# SDRAM_DDR3_2x16.net
KiCad netlist of a schematic drawn in Altium Designer
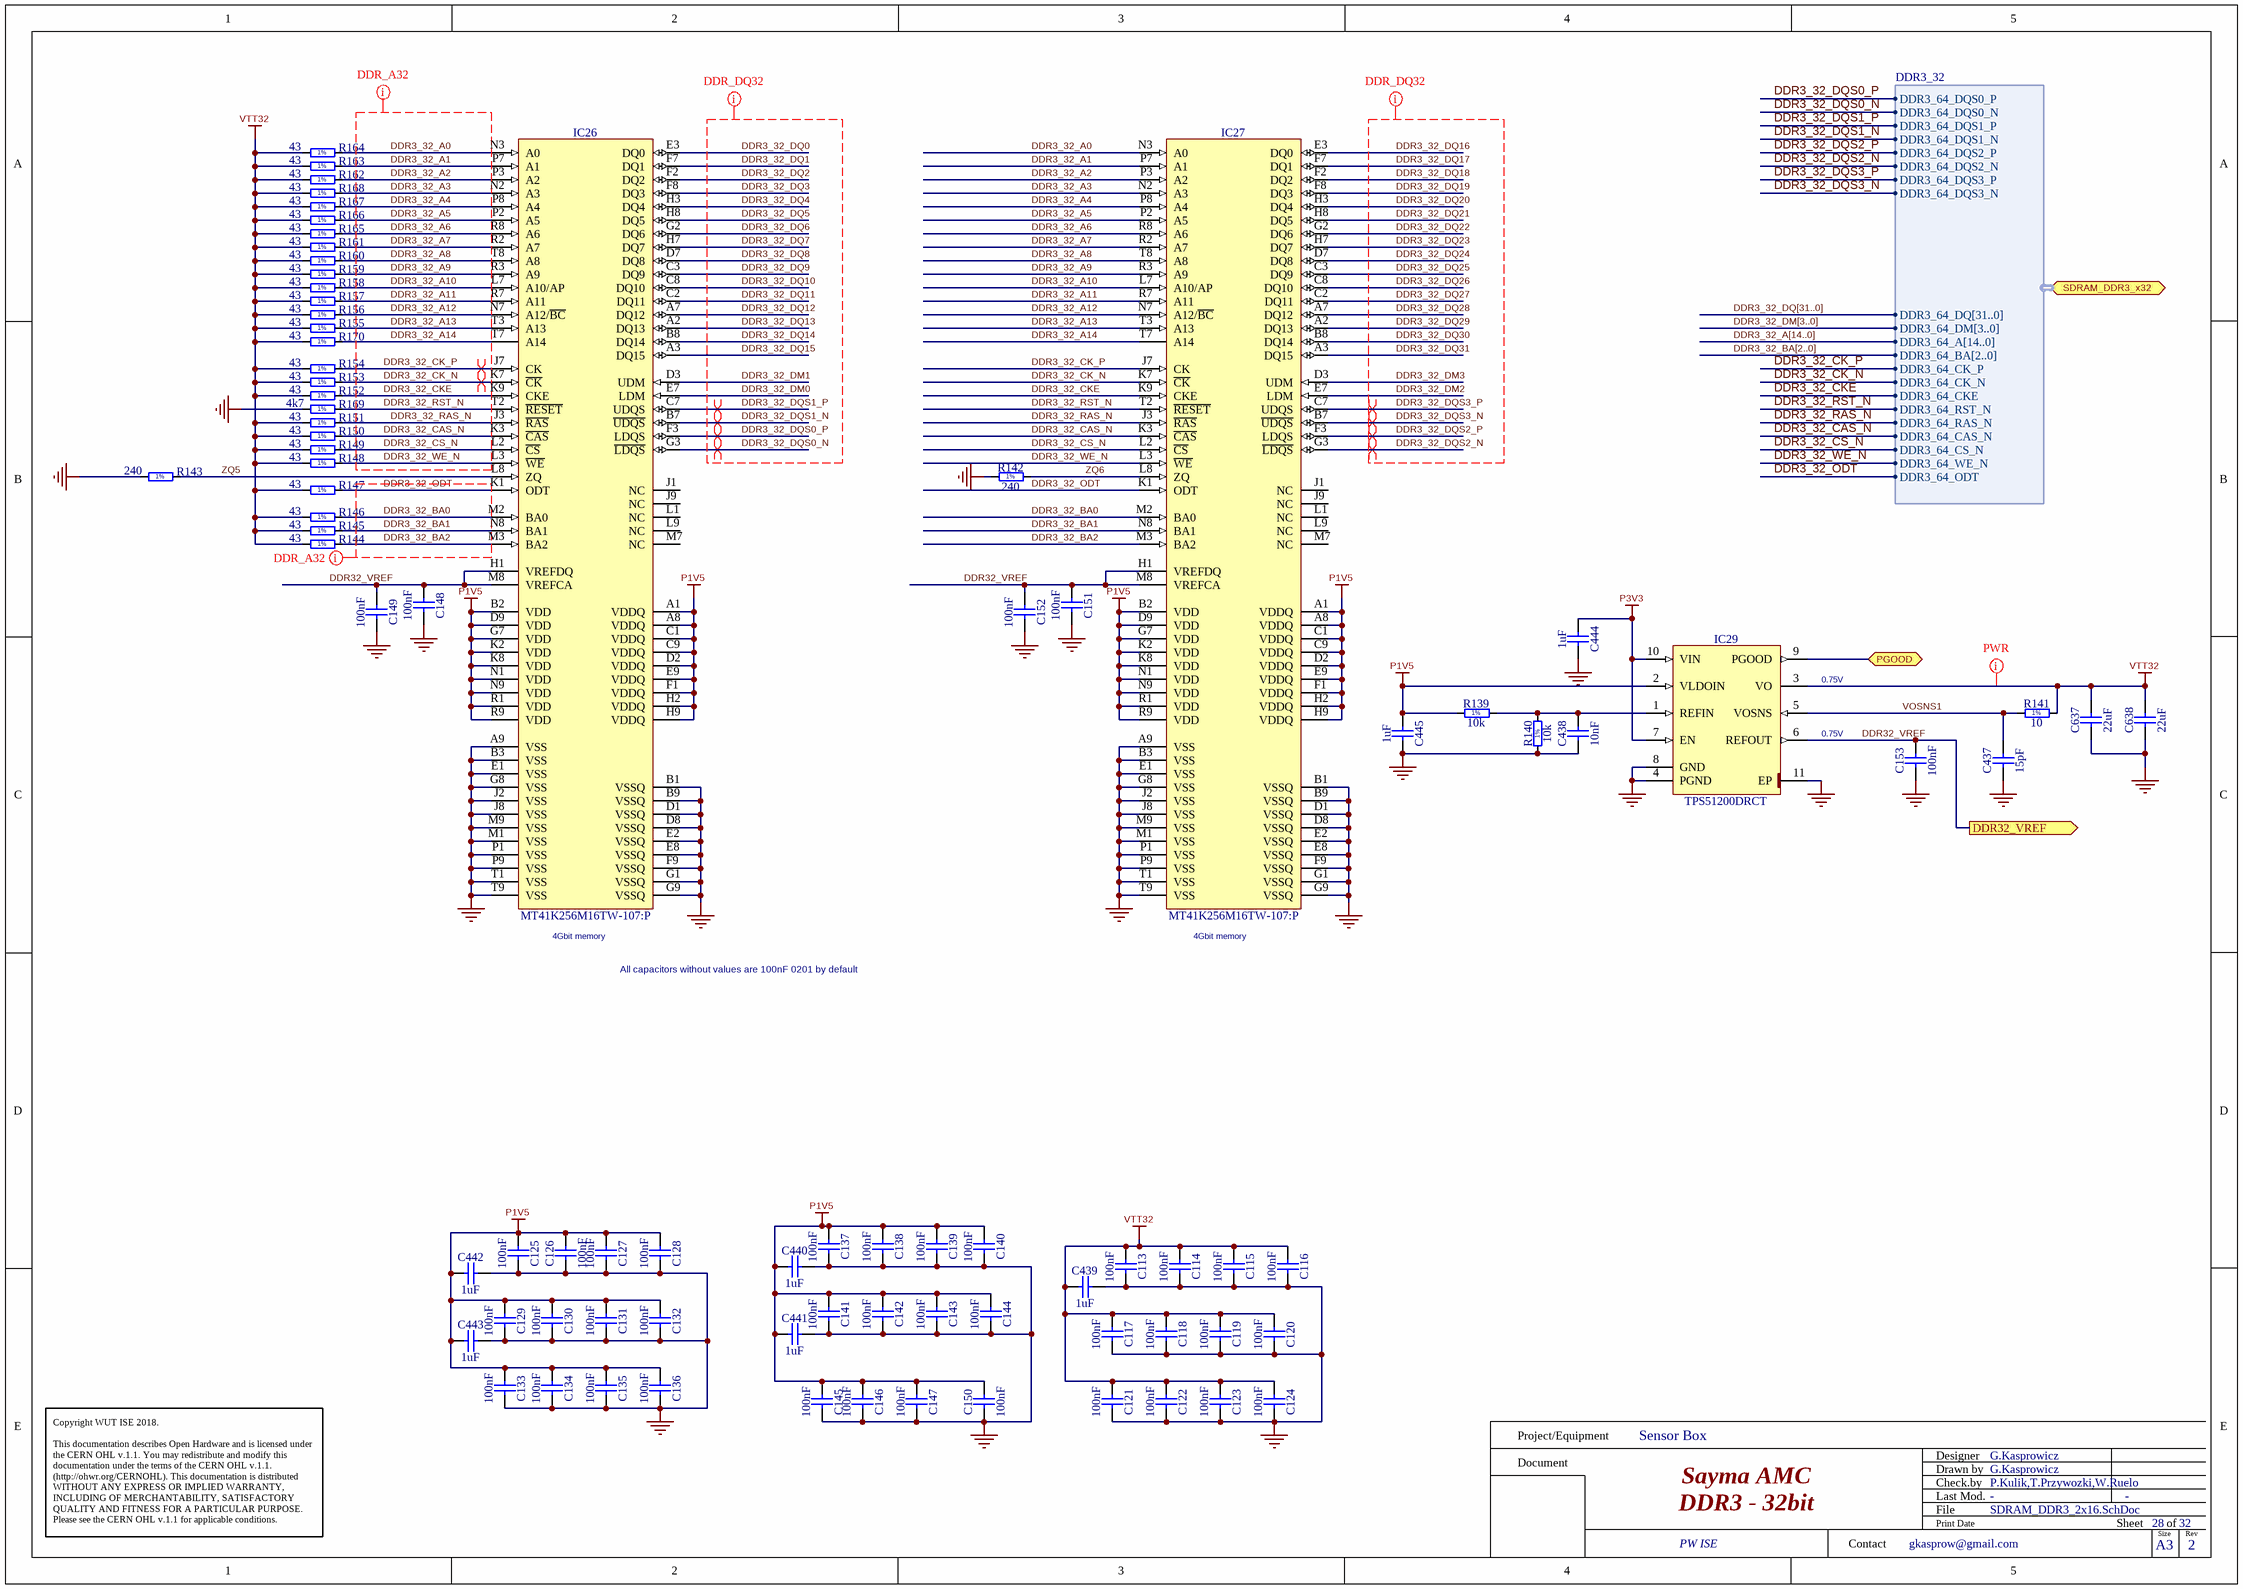
[diagram p0: SDRAM_DDR3_2x16.SchDoc]

(export (version "E")
  (design (tool "Eeschema 10.0.6"))
  (components
    (comp (ref "C113")
      (value "100nF")
      (footprint "CAPC0603X33N")
      (description "Non-polarised capacitor")
      (fields
        (field (name "MANUFACTURER PART NUMBER") "CC0201_100NF_6.3V_10%_X5R")
        (field (name "MANUFACTURER") "GENERIC")
        (field (name "AUTHOR") "CERN DEM JLC")
      )
      (libsource (lib "Capacitors") (part "Capacitor - non polarized"))
    )
    (comp (ref "C114")
      (value "100nF")
      (footprint "CAPC0603X33N")
      (description "Non-polarised capacitor")
      (fields
        (field (name "MANUFACTURER PART NUMBER") "CC0201_100NF_6.3V_10%_X5R")
        (field (name "MANUFACTURER") "GENERIC")
        (field (name "AUTHOR") "CERN DEM JLC")
      )
      (libsource (lib "Capacitors") (part "Capacitor - non polarized"))
    )
    (comp (ref "C115")
      (value "100nF")
      (footprint "CAPC0603X33N")
      (description "Non-polarised capacitor")
      (fields
        (field (name "MANUFACTURER PART NUMBER") "CC0201_100NF_6.3V_10%_X5R")
        (field (name "MANUFACTURER") "GENERIC")
        (field (name "AUTHOR") "CERN DEM JLC")
      )
      (libsource (lib "Capacitors") (part "Capacitor - non polarized"))
    )
    (comp (ref "C116")
      (value "100nF")
      (footprint "CAPC0603X33N")
      (description "Non-polarised capacitor")
      (fields
        (field (name "MANUFACTURER PART NUMBER") "CC0201_100NF_6.3V_10%_X5R")
        (field (name "MANUFACTURER") "GENERIC")
        (field (name "AUTHOR") "CERN DEM JLC")
      )
      (libsource (lib "Capacitors") (part "Capacitor - non polarized"))
    )
    (comp (ref "C117")
      (value "100nF")
      (footprint "CAPC0603X33N")
      (description "Non-polarised capacitor")
      (fields
        (field (name "MANUFACTURER PART NUMBER") "CC0201_100NF_6.3V_10%_X5R")
        (field (name "MANUFACTURER") "GENERIC")
        (field (name "AUTHOR") "CERN DEM JLC")
      )
      (libsource (lib "Capacitors") (part "Capacitor - non polarized"))
    )
    (comp (ref "C118")
      (value "100nF")
      (footprint "CAPC0603X33N")
      (description "Non-polarised capacitor")
      (fields
        (field (name "MANUFACTURER PART NUMBER") "CC0201_100NF_6.3V_10%_X5R")
        (field (name "MANUFACTURER") "GENERIC")
        (field (name "AUTHOR") "CERN DEM JLC")
      )
      (libsource (lib "Capacitors") (part "Capacitor - non polarized"))
    )
    (comp (ref "C119")
      (value "100nF")
      (footprint "CAPC0603X33N")
      (description "Non-polarised capacitor")
      (fields
        (field (name "MANUFACTURER PART NUMBER") "CC0201_100NF_6.3V_10%_X5R")
        (field (name "MANUFACTURER") "GENERIC")
        (field (name "AUTHOR") "CERN DEM JLC")
      )
      (libsource (lib "Capacitors") (part "Capacitor - non polarized"))
    )
    (comp (ref "C120")
      (value "100nF")
      (footprint "CAPC0603X33N")
      (description "Non-polarised capacitor")
      (fields
        (field (name "MANUFACTURER PART NUMBER") "CC0201_100NF_6.3V_10%_X5R")
        (field (name "MANUFACTURER") "GENERIC")
        (field (name "AUTHOR") "CERN DEM JLC")
      )
      (libsource (lib "Capacitors") (part "Capacitor - non polarized"))
    )
    (comp (ref "C121")
      (value "100nF")
      (footprint "CAPC0603X33N")
      (description "Non-polarised capacitor")
      (fields
        (field (name "MANUFACTURER PART NUMBER") "CC0201_100NF_6.3V_10%_X5R")
        (field (name "MANUFACTURER") "GENERIC")
        (field (name "AUTHOR") "CERN DEM JLC")
      )
      (libsource (lib "Capacitors") (part "Capacitor - non polarized"))
    )
    (comp (ref "C122")
      (value "100nF")
      (footprint "CAPC0603X33N")
      (description "Non-polarised capacitor")
      (fields
        (field (name "MANUFACTURER PART NUMBER") "CC0201_100NF_6.3V_10%_X5R")
        (field (name "MANUFACTURER") "GENERIC")
        (field (name "AUTHOR") "CERN DEM JLC")
      )
      (libsource (lib "Capacitors") (part "Capacitor - non polarized"))
    )
    (comp (ref "C123")
      (value "100nF")
      (footprint "CAPC0603X33N")
      (description "Non-polarised capacitor")
      (fields
        (field (name "MANUFACTURER PART NUMBER") "CC0201_100NF_6.3V_10%_X5R")
        (field (name "MANUFACTURER") "GENERIC")
        (field (name "AUTHOR") "CERN DEM JLC")
      )
      (libsource (lib "Capacitors") (part "Capacitor - non polarized"))
    )
    (comp (ref "C124")
      (value "100nF")
      (footprint "CAPC0603X33N")
      (description "Non-polarised capacitor")
      (fields
        (field (name "MANUFACTURER PART NUMBER") "CC0201_100NF_6.3V_10%_X5R")
        (field (name "MANUFACTURER") "GENERIC")
        (field (name "AUTHOR") "CERN DEM JLC")
      )
      (libsource (lib "Capacitors") (part "Capacitor - non polarized"))
    )
    (comp (ref "C125")
      (value "100nF")
      (footprint "CAPC0603X33N")
      (description "Non-polarised capacitor")
      (fields
        (field (name "MANUFACTURER PART NUMBER") "CC0201_100NF_6.3V_10%_X5R")
        (field (name "MANUFACTURER") "GENERIC")
        (field (name "AUTHOR") "CERN DEM JLC")
      )
      (libsource (lib "Capacitors") (part "Capacitor - non polarized"))
    )
    (comp (ref "C126")
      (value "100nF")
      (footprint "CAPC0603X33N")
      (description "Non-polarised capacitor")
      (fields
        (field (name "MANUFACTURER PART NUMBER") "CC0201_100NF_6.3V_10%_X5R")
        (field (name "MANUFACTURER") "GENERIC")
        (field (name "AUTHOR") "CERN DEM JLC")
      )
      (libsource (lib "Capacitors") (part "Capacitor - non polarized"))
    )
    (comp (ref "C127")
      (value "100nF")
      (footprint "CAPC0603X33N")
      (description "Non-polarised capacitor")
      (fields
        (field (name "MANUFACTURER PART NUMBER") "CC0201_100NF_6.3V_10%_X5R")
        (field (name "MANUFACTURER") "GENERIC")
        (field (name "AUTHOR") "CERN DEM JLC")
      )
      (libsource (lib "Capacitors") (part "Capacitor - non polarized"))
    )
    (comp (ref "C128")
      (value "100nF")
      (footprint "CAPC0603X33N")
      (description "Non-polarised capacitor")
      (fields
        (field (name "MANUFACTURER PART NUMBER") "CC0201_100NF_6.3V_10%_X5R")
        (field (name "MANUFACTURER") "GENERIC")
        (field (name "AUTHOR") "CERN DEM JLC")
      )
      (libsource (lib "Capacitors") (part "Capacitor - non polarized"))
    )
    (comp (ref "C129")
      (value "100nF")
      (footprint "CAPC0603X33N")
      (description "Non-polarised capacitor")
      (fields
        (field (name "MANUFACTURER PART NUMBER") "CC0201_100NF_6.3V_10%_X5R")
        (field (name "MANUFACTURER") "GENERIC")
        (field (name "AUTHOR") "CERN DEM JLC")
      )
      (libsource (lib "Capacitors") (part "Capacitor - non polarized"))
    )
    (comp (ref "C130")
      (value "100nF")
      (footprint "CAPC0603X33N")
      (description "Non-polarised capacitor")
      (fields
        (field (name "MANUFACTURER PART NUMBER") "CC0201_100NF_6.3V_10%_X5R")
        (field (name "MANUFACTURER") "GENERIC")
        (field (name "AUTHOR") "CERN DEM JLC")
      )
      (libsource (lib "Capacitors") (part "Capacitor - non polarized"))
    )
    (comp (ref "C131")
      (value "100nF")
      (footprint "CAPC0603X33N")
      (description "Non-polarised capacitor")
      (fields
        (field (name "MANUFACTURER PART NUMBER") "CC0201_100NF_6.3V_10%_X5R")
        (field (name "MANUFACTURER") "GENERIC")
        (field (name "AUTHOR") "CERN DEM JLC")
      )
      (libsource (lib "Capacitors") (part "Capacitor - non polarized"))
    )
    (comp (ref "C132")
      (value "100nF")
      (footprint "CAPC0603X33N")
      (description "Non-polarised capacitor")
      (fields
        (field (name "MANUFACTURER PART NUMBER") "CC0201_100NF_6.3V_10%_X5R")
        (field (name "MANUFACTURER") "GENERIC")
        (field (name "AUTHOR") "CERN DEM JLC")
      )
      (libsource (lib "Capacitors") (part "Capacitor - non polarized"))
    )
    (comp (ref "C133")
      (value "100nF")
      (footprint "CAPC0603X33N")
      (description "Non-polarised capacitor")
      (fields
        (field (name "MANUFACTURER PART NUMBER") "CC0201_100NF_6.3V_10%_X5R")
        (field (name "MANUFACTURER") "GENERIC")
        (field (name "AUTHOR") "CERN DEM JLC")
      )
      (libsource (lib "Capacitors") (part "Capacitor - non polarized"))
    )
    (comp (ref "C134")
      (value "100nF")
      (footprint "CAPC0603X33N")
      (description "Non-polarised capacitor")
      (fields
        (field (name "MANUFACTURER PART NUMBER") "CC0201_100NF_6.3V_10%_X5R")
        (field (name "MANUFACTURER") "GENERIC")
        (field (name "AUTHOR") "CERN DEM JLC")
      )
      (libsource (lib "Capacitors") (part "Capacitor - non polarized"))
    )
    (comp (ref "C135")
      (value "100nF")
      (footprint "CAPC0603X33N")
      (description "Non-polarised capacitor")
      (fields
        (field (name "MANUFACTURER PART NUMBER") "CC0201_100NF_6.3V_10%_X5R")
        (field (name "MANUFACTURER") "GENERIC")
        (field (name "AUTHOR") "CERN DEM JLC")
      )
      (libsource (lib "Capacitors") (part "Capacitor - non polarized"))
    )
    (comp (ref "C136")
      (value "100nF")
      (footprint "CAPC0603X33N")
      (description "Non-polarised capacitor")
      (fields
        (field (name "MANUFACTURER PART NUMBER") "CC0201_100NF_6.3V_10%_X5R")
        (field (name "MANUFACTURER") "GENERIC")
        (field (name "AUTHOR") "CERN DEM JLC")
      )
      (libsource (lib "Capacitors") (part "Capacitor - non polarized"))
    )
    (comp (ref "C137")
      (value "100nF")
      (footprint "CAPC0603X33N")
      (description "Non-polarised capacitor")
      (fields
        (field (name "MANUFACTURER PART NUMBER") "CC0201_100NF_6.3V_10%_X5R")
        (field (name "MANUFACTURER") "GENERIC")
        (field (name "AUTHOR") "CERN DEM JLC")
      )
      (libsource (lib "Capacitors") (part "Capacitor - non polarized"))
    )
    (comp (ref "C138")
      (value "100nF")
      (footprint "CAPC0603X33N")
      (description "Non-polarised capacitor")
      (fields
        (field (name "MANUFACTURER PART NUMBER") "CC0201_100NF_6.3V_10%_X5R")
        (field (name "MANUFACTURER") "GENERIC")
        (field (name "AUTHOR") "CERN DEM JLC")
      )
      (libsource (lib "Capacitors") (part "Capacitor - non polarized"))
    )
    (comp (ref "C139")
      (value "100nF")
      (footprint "CAPC0603X33N")
      (description "Non-polarised capacitor")
      (fields
        (field (name "MANUFACTURER PART NUMBER") "CC0201_100NF_6.3V_10%_X5R")
        (field (name "MANUFACTURER") "GENERIC")
        (field (name "AUTHOR") "CERN DEM JLC")
      )
      (libsource (lib "Capacitors") (part "Capacitor - non polarized"))
    )
    (comp (ref "C140")
      (value "100nF")
      (footprint "CAPC0603X33N")
      (description "Non-polarised capacitor")
      (fields
        (field (name "MANUFACTURER PART NUMBER") "CC0201_100NF_6.3V_10%_X5R")
        (field (name "MANUFACTURER") "GENERIC")
        (field (name "AUTHOR") "CERN DEM JLC")
      )
      (libsource (lib "Capacitors") (part "Capacitor - non polarized"))
    )
    (comp (ref "C141")
      (value "100nF")
      (footprint "CAPC0603X33N")
      (description "Non-polarised capacitor")
      (fields
        (field (name "MANUFACTURER PART NUMBER") "CC0201_100NF_6.3V_10%_X5R")
        (field (name "MANUFACTURER") "GENERIC")
        (field (name "AUTHOR") "CERN DEM JLC")
      )
      (libsource (lib "Capacitors") (part "Capacitor - non polarized"))
    )
    (comp (ref "C142")
      (value "100nF")
      (footprint "CAPC0603X33N")
      (description "Non-polarised capacitor")
      (fields
        (field (name "MANUFACTURER PART NUMBER") "CC0201_100NF_6.3V_10%_X5R")
        (field (name "MANUFACTURER") "GENERIC")
        (field (name "AUTHOR") "CERN DEM JLC")
      )
      (libsource (lib "Capacitors") (part "Capacitor - non polarized"))
    )
    (comp (ref "C143")
      (value "100nF")
      (footprint "CAPC0603X33N")
      (description "Non-polarised capacitor")
      (fields
        (field (name "MANUFACTURER PART NUMBER") "CC0201_100NF_6.3V_10%_X5R")
        (field (name "MANUFACTURER") "GENERIC")
        (field (name "AUTHOR") "CERN DEM JLC")
      )
      (libsource (lib "Capacitors") (part "Capacitor - non polarized"))
    )
    (comp (ref "C144")
      (value "100nF")
      (footprint "CAPC0603X33N")
      (description "Non-polarised capacitor")
      (fields
        (field (name "MANUFACTURER PART NUMBER") "CC0201_100NF_6.3V_10%_X5R")
        (field (name "MANUFACTURER") "GENERIC")
        (field (name "AUTHOR") "CERN DEM JLC")
      )
      (libsource (lib "Capacitors") (part "Capacitor - non polarized"))
    )
    (comp (ref "C145")
      (value "100nF")
      (footprint "CAPC0603X33N")
      (description "Non-polarised capacitor")
      (fields
        (field (name "MANUFACTURER PART NUMBER") "CC0201_100NF_6.3V_10%_X5R")
        (field (name "MANUFACTURER") "GENERIC")
        (field (name "AUTHOR") "CERN DEM JLC")
      )
      (libsource (lib "Capacitors") (part "Capacitor - non polarized"))
    )
    (comp (ref "C146")
      (value "100nF")
      (footprint "CAPC0603X33N")
      (description "Non-polarised capacitor")
      (fields
        (field (name "MANUFACTURER PART NUMBER") "CC0201_100NF_6.3V_10%_X5R")
        (field (name "MANUFACTURER") "GENERIC")
        (field (name "AUTHOR") "CERN DEM JLC")
      )
      (libsource (lib "Capacitors") (part "Capacitor - non polarized"))
    )
    (comp (ref "C147")
      (value "100nF")
      (footprint "CAPC0603X33N")
      (description "Non-polarised capacitor")
      (fields
        (field (name "MANUFACTURER PART NUMBER") "CC0201_100NF_6.3V_10%_X5R")
        (field (name "MANUFACTURER") "GENERIC")
        (field (name "AUTHOR") "CERN DEM JLC")
      )
      (libsource (lib "Capacitors") (part "Capacitor - non polarized"))
    )
    (comp (ref "C148")
      (value "100nF")
      (footprint "CAPC0603X33N")
      (description "Non-polarised capacitor")
      (fields
        (field (name "MANUFACTURER PART NUMBER") "CC0201_100NF_6.3V_10%_X5R")
        (field (name "MANUFACTURER") "GENERIC")
        (field (name "AUTHOR") "CERN DEM JLC")
      )
      (libsource (lib "Capacitors") (part "Capacitor - non polarized"))
    )
    (comp (ref "C149")
      (value "100nF")
      (footprint "CAPC0603X33N")
      (description "Non-polarised capacitor")
      (fields
        (field (name "MANUFACTURER PART NUMBER") "CC0201_100NF_6.3V_10%_X5R")
        (field (name "MANUFACTURER") "GENERIC")
        (field (name "AUTHOR") "CERN DEM JLC")
      )
      (libsource (lib "Capacitors") (part "Capacitor - non polarized"))
    )
    (comp (ref "C150")
      (value "100nF")
      (footprint "CAPC0603X33N")
      (description "Non-polarised capacitor")
      (fields
        (field (name "MANUFACTURER PART NUMBER") "CC0201_100NF_6.3V_10%_X5R")
        (field (name "MANUFACTURER") "GENERIC")
        (field (name "AUTHOR") "CERN DEM JLC")
      )
      (libsource (lib "Capacitors") (part "Capacitor - non polarized"))
    )
    (comp (ref "C151")
      (value "100nF")
      (footprint "CAPC0603X33N")
      (description "Non-polarised capacitor")
      (fields
        (field (name "MANUFACTURER PART NUMBER") "CC0201_100NF_6.3V_10%_X5R")
        (field (name "MANUFACTURER") "GENERIC")
        (field (name "AUTHOR") "CERN DEM JLC")
      )
      (libsource (lib "Capacitors") (part "Capacitor - non polarized"))
    )
    (comp (ref "C152")
      (value "100nF")
      (footprint "CAPC0603X33N")
      (description "Non-polarised capacitor")
      (fields
        (field (name "MANUFACTURER PART NUMBER") "CC0201_100NF_6.3V_10%_X5R")
        (field (name "MANUFACTURER") "GENERIC")
        (field (name "AUTHOR") "CERN DEM JLC")
      )
      (libsource (lib "Capacitors") (part "Capacitor - non polarized"))
    )
    (comp (ref "C153")
      (value "100nF")
      (footprint "CAPC0603X33N")
      (description "Non-polarised capacitor")
      (fields
        (field (name "MANUFACTURER PART NUMBER") "CC0201_100NF_6.3V_10%_X5R")
        (field (name "MANUFACTURER") "GENERIC")
        (field (name "AUTHOR") "CERN DEM JLC")
      )
      (libsource (lib "Capacitors") (part "Capacitor - non polarized"))
    )
    (comp (ref "C437")
      (value "15pF")
      (footprint "CAPC1005X55N")
      (description "Non-polarised capacitor")
      (fields
        (field (name "MANUFACTURER PART NUMBER") "CC0402_15PF_50V_5%_C0G")
        (field (name "MANUFACTURER") "GENERIC")
        (field (name "AUTHOR") "CERN DEM JLC")
      )
      (libsource (lib "Capacitors") (part "Capacitor - non polarized"))
    )
    (comp (ref "C438")
      (value "10nF")
      (footprint "CAPC1005X55N")
      (description "Non-polarised capacitor")
      (fields
        (field (name "MANUFACTURER PART NUMBER") "CC0402_10NF_25V_10%_X7R")
        (field (name "MANUFACTURER") "GENERIC")
        (field (name "AUTHOR") "CERN DEM JLC")
      )
      (libsource (lib "Capacitors") (part "Capacitor - non polarized"))
    )
    (comp (ref "C439")
      (value "1uF")
      (footprint "CAPC1005X55N")
      (description "Non-polarised capacitor")
      (fields
        (field (name "MANUFACTURER PART NUMBER") "CC0402_1UF_16V_10%_X5R")
        (field (name "MANUFACTURER") "GENERIC")
        (field (name "AUTHOR") "CERN DEM JLC")
      )
      (libsource (lib "Capacitors") (part "Capacitor - non polarized"))
    )
    (comp (ref "C440")
      (value "1uF")
      (footprint "CAPC1005X55N")
      (description "Non-polarised capacitor")
      (fields
        (field (name "MANUFACTURER PART NUMBER") "CC0402_1UF_16V_10%_X5R")
        (field (name "MANUFACTURER") "GENERIC")
        (field (name "AUTHOR") "CERN DEM JLC")
      )
      (libsource (lib "Capacitors") (part "Capacitor - non polarized"))
    )
    (comp (ref "C441")
      (value "1uF")
      (footprint "CAPC1005X55N")
      (description "Non-polarised capacitor")
      (fields
        (field (name "MANUFACTURER PART NUMBER") "CC0402_1UF_16V_10%_X5R")
        (field (name "MANUFACTURER") "GENERIC")
        (field (name "AUTHOR") "CERN DEM JLC")
      )
      (libsource (lib "Capacitors") (part "Capacitor - non polarized"))
    )
    (comp (ref "C442")
      (value "1uF")
      (footprint "CAPC1005X55N")
      (description "Non-polarised capacitor")
      (fields
        (field (name "MANUFACTURER PART NUMBER") "CC0402_1UF_16V_10%_X5R")
        (field (name "MANUFACTURER") "GENERIC")
        (field (name "AUTHOR") "CERN DEM JLC")
      )
      (libsource (lib "Capacitors") (part "Capacitor - non polarized"))
    )
    (comp (ref "C443")
      (value "1uF")
      (footprint "CAPC1005X55N")
      (description "Non-polarised capacitor")
      (fields
        (field (name "MANUFACTURER PART NUMBER") "CC0402_1UF_16V_10%_X5R")
        (field (name "MANUFACTURER") "GENERIC")
        (field (name "AUTHOR") "CERN DEM JLC")
      )
      (libsource (lib "Capacitors") (part "Capacitor - non polarized"))
    )
    (comp (ref "C444")
      (value "1uF")
      (footprint "CAPC1005X55N")
      (description "Non-polarised capacitor")
      (fields
        (field (name "MANUFACTURER PART NUMBER") "CC0402_1UF_16V_10%_X5R")
        (field (name "MANUFACTURER") "GENERIC")
        (field (name "AUTHOR") "CERN DEM JLC")
      )
      (libsource (lib "Capacitors") (part "Capacitor - non polarized"))
    )
    (comp (ref "C445")
      (value "1uF")
      (footprint "CAPC1005X55N")
      (description "Non-polarised capacitor")
      (fields
        (field (name "MANUFACTURER PART NUMBER") "CC0402_1UF_16V_10%_X5R")
        (field (name "MANUFACTURER") "GENERIC")
        (field (name "AUTHOR") "CERN DEM JLC")
      )
      (libsource (lib "Capacitors") (part "Capacitor - non polarized"))
    )
    (comp (ref "C637")
      (value "22uF")
      (footprint "CAPC2012X135N")
      (description "Non-polarised capacitor")
      (fields
        (field (name "MANUFACTURER PART NUMBER") "CC0805_22UF_10V_+80%-20%_Y5V")
        (field (name "MANUFACTURER") "GENERIC")
        (field (name "AUTHOR") "CERN DEM JLC")
      )
      (libsource (lib "Capacitors") (part "Capacitor - non polarized"))
    )
    (comp (ref "C638")
      (value "22uF")
      (footprint "CAPC2012X135N")
      (description "Non-polarised capacitor")
      (fields
        (field (name "MANUFACTURER PART NUMBER") "CC0805_22UF_10V_+80%-20%_Y5V")
        (field (name "MANUFACTURER") "GENERIC")
        (field (name "AUTHOR") "CERN DEM JLC")
      )
      (libsource (lib "Capacitors") (part "Capacitor - non polarized"))
    )
    (comp (ref "IC26")
      (value "MT41K256M16TW-107:P")
      (footprint "BGA96C80P9X16_800X1400X120")
      (description "32 Meg x 16 x 8 Banks DDR3L SDRAM")
      (fields (field (name "MANUFACTURER") "MICRON TECHNOLOGY") (field (name "AUTHOR") "CERN DEM MR"))
      (libsource (lib "ICs And Semiconductors") (part "MT41K256M16TW-107{colon}P"))
    )
    (comp (ref "IC27")
      (value "MT41K256M16TW-107:P")
      (footprint "BGA96C80P9X16_800X1400X120")
      (description "32 Meg x 16 x 8 Banks DDR3L SDRAM")
      (fields (field (name "MANUFACTURER") "MICRON TECHNOLOGY") (field (name "AUTHOR") "CERN DEM MR"))
      (libsource (lib "ICs And Semiconductors") (part "MT41K256M16TW-107{colon}P"))
    )
    (comp (ref "IC29")
      (value "TPS51200DRCT")
      (footprint "TEXAS_DRC (S-PVSON-N10)")
      (description "Sink/Source DDR Termination Regulator")
      (fields (field (name "MANUFACTURER") "TEXAS INSTRUMENTS") (field (name "AUTHOR") "CERN DEM JLC"))
      (libsource (lib "ICs And Semiconductors") (part "TPS51200DRC"))
    )
    (comp (ref "R139")
      (value "10k")
      (footprint "RESC1005X40N")
      (description "Resistor - 1%")
      (fields
        (field (name "MANUFACTURER PART NUMBER") "R0402_10K_1%_0.0625W_100PPM")
        (field (name "MANUFACTURER") "GENERIC")
        (field (name "AUTHOR") "CERN DEM JLC")
      )
      (libsource (lib "Resistors") (part "Resistor - 1%"))
    )
    (comp (ref "R140")
      (value "10k")
      (footprint "RESC1005X40N")
      (description "Resistor - 1%")
      (fields
        (field (name "MANUFACTURER PART NUMBER") "R0402_10K_1%_0.0625W_100PPM")
        (field (name "MANUFACTURER") "GENERIC")
        (field (name "AUTHOR") "CERN DEM JLC")
      )
      (libsource (lib "Resistors") (part "Resistor - 1%"))
    )
    (comp (ref "R141")
      (value "10")
      (footprint "RESC1005X40N")
      (description "Resistor - 1%")
      (fields
        (field (name "MANUFACTURER PART NUMBER") "R0402_10R_1%_0.0625W_200PPM")
        (field (name "MANUFACTURER") "GENERIC")
        (field (name "AUTHOR") "CERN DEM JLC")
      )
      (libsource (lib "Resistors") (part "Resistor - 1%"))
    )
    (comp (ref "R142")
      (value "240")
      (footprint "RESC1005X40N")
      (description "Resistor - 1%")
      (fields
        (field (name "MANUFACTURER PART NUMBER") "R0402_240R_1%_0.0625W_100PPM")
        (field (name "MANUFACTURER") "GENERIC")
        (field (name "AUTHOR") "CERN DEM JLC")
      )
      (libsource (lib "Resistors") (part "Resistor - 1%"))
    )
    (comp (ref "R143")
      (value "240")
      (footprint "RESC1005X40N")
      (description "Resistor - 1%")
      (fields
        (field (name "MANUFACTURER PART NUMBER") "R0402_240R_1%_0.0625W_100PPM")
        (field (name "MANUFACTURER") "GENERIC")
        (field (name "AUTHOR") "CERN DEM JLC")
      )
      (libsource (lib "Resistors") (part "Resistor - 1%"))
    )
    (comp (ref "R144")
      (value "43")
      (footprint "RESC1005X40N")
      (description "Resistor - 1%")
      (fields
        (field (name "MANUFACTURER PART NUMBER") "R0402_43R_1%_0.0625W_100PPM")
        (field (name "MANUFACTURER") "GENERIC")
        (field (name "AUTHOR") "CERN DEM JLC")
      )
      (libsource (lib "Resistors") (part "Resistor - 1%"))
    )
    (comp (ref "R145")
      (value "43")
      (footprint "RESC1005X40N")
      (description "Resistor - 1%")
      (fields
        (field (name "MANUFACTURER PART NUMBER") "R0402_43R_1%_0.0625W_100PPM")
        (field (name "MANUFACTURER") "GENERIC")
        (field (name "AUTHOR") "CERN DEM JLC")
      )
      (libsource (lib "Resistors") (part "Resistor - 1%"))
    )
    (comp (ref "R146")
      (value "43")
      (footprint "RESC1005X40N")
      (description "Resistor - 1%")
      (fields
        (field (name "MANUFACTURER PART NUMBER") "R0402_43R_1%_0.0625W_100PPM")
        (field (name "MANUFACTURER") "GENERIC")
        (field (name "AUTHOR") "CERN DEM JLC")
      )
      (libsource (lib "Resistors") (part "Resistor - 1%"))
    )
    (comp (ref "R147")
      (value "43")
      (footprint "RESC1005X40N")
      (description "Resistor - 1%")
      (fields
        (field (name "MANUFACTURER PART NUMBER") "R0402_43R_1%_0.0625W_100PPM")
        (field (name "MANUFACTURER") "GENERIC")
        (field (name "AUTHOR") "CERN DEM JLC")
      )
      (libsource (lib "Resistors") (part "Resistor - 1%"))
    )
    (comp (ref "R148")
      (value "43")
      (footprint "RESC1005X40N")
      (description "Resistor - 1%")
      (fields
        (field (name "MANUFACTURER PART NUMBER") "R0402_43R_1%_0.0625W_100PPM")
        (field (name "MANUFACTURER") "GENERIC")
        (field (name "AUTHOR") "CERN DEM JLC")
      )
      (libsource (lib "Resistors") (part "Resistor - 1%"))
    )
    (comp (ref "R149")
      (value "43")
      (footprint "RESC1005X40N")
      (description "Resistor - 1%")
      (fields
        (field (name "MANUFACTURER PART NUMBER") "R0402_43R_1%_0.0625W_100PPM")
        (field (name "MANUFACTURER") "GENERIC")
        (field (name "AUTHOR") "CERN DEM JLC")
      )
      (libsource (lib "Resistors") (part "Resistor - 1%"))
    )
    (comp (ref "R150")
      (value "43")
      (footprint "RESC1005X40N")
      (description "Resistor - 1%")
      (fields
        (field (name "MANUFACTURER PART NUMBER") "R0402_43R_1%_0.0625W_100PPM")
        (field (name "MANUFACTURER") "GENERIC")
        (field (name "AUTHOR") "CERN DEM JLC")
      )
      (libsource (lib "Resistors") (part "Resistor - 1%"))
    )
    (comp (ref "R151")
      (value "43")
      (footprint "RESC1005X40N")
      (description "Resistor - 1%")
      (fields
        (field (name "MANUFACTURER PART NUMBER") "R0402_43R_1%_0.0625W_100PPM")
        (field (name "MANUFACTURER") "GENERIC")
        (field (name "AUTHOR") "CERN DEM JLC")
      )
      (libsource (lib "Resistors") (part "Resistor - 1%"))
    )
    (comp (ref "R152")
      (value "43")
      (footprint "RESC1005X40N")
      (description "Resistor - 1%")
      (fields
        (field (name "MANUFACTURER PART NUMBER") "R0402_43R_1%_0.0625W_100PPM")
        (field (name "MANUFACTURER") "GENERIC")
        (field (name "AUTHOR") "CERN DEM JLC")
      )
      (libsource (lib "Resistors") (part "Resistor - 1%"))
    )
    (comp (ref "R153")
      (value "43")
      (footprint "RESC1005X40N")
      (description "Resistor - 1%")
      (fields
        (field (name "MANUFACTURER PART NUMBER") "R0402_43R_1%_0.0625W_100PPM")
        (field (name "MANUFACTURER") "GENERIC")
        (field (name "AUTHOR") "CERN DEM JLC")
      )
      (libsource (lib "Resistors") (part "Resistor - 1%"))
    )
    (comp (ref "R154")
      (value "43")
      (footprint "RESC1005X40N")
      (description "Resistor - 1%")
      (fields
        (field (name "MANUFACTURER PART NUMBER") "R0402_43R_1%_0.0625W_100PPM")
        (field (name "MANUFACTURER") "GENERIC")
        (field (name "AUTHOR") "CERN DEM JLC")
      )
      (libsource (lib "Resistors") (part "Resistor - 1%"))
    )
    (comp (ref "R155")
      (value "43")
      (footprint "RESC1005X40N")
      (description "Resistor - 1%")
      (fields
        (field (name "MANUFACTURER PART NUMBER") "R0402_43R_1%_0.0625W_100PPM")
        (field (name "MANUFACTURER") "GENERIC")
        (field (name "AUTHOR") "CERN DEM JLC")
      )
      (libsource (lib "Resistors") (part "Resistor - 1%"))
    )
    (comp (ref "R156")
      (value "43")
      (footprint "RESC1005X40N")
      (description "Resistor - 1%")
      (fields
        (field (name "MANUFACTURER PART NUMBER") "R0402_43R_1%_0.0625W_100PPM")
        (field (name "MANUFACTURER") "GENERIC")
        (field (name "AUTHOR") "CERN DEM JLC")
      )
      (libsource (lib "Resistors") (part "Resistor - 1%"))
    )
    (comp (ref "R157")
      (value "43")
      (footprint "RESC1005X40N")
      (description "Resistor - 1%")
      (fields
        (field (name "MANUFACTURER PART NUMBER") "R0402_43R_1%_0.0625W_100PPM")
        (field (name "MANUFACTURER") "GENERIC")
        (field (name "AUTHOR") "CERN DEM JLC")
      )
      (libsource (lib "Resistors") (part "Resistor - 1%"))
    )
    (comp (ref "R158")
      (value "43")
      (footprint "RESC1005X40N")
      (description "Resistor - 1%")
      (fields
        (field (name "MANUFACTURER PART NUMBER") "R0402_43R_1%_0.0625W_100PPM")
        (field (name "MANUFACTURER") "GENERIC")
        (field (name "AUTHOR") "CERN DEM JLC")
      )
      (libsource (lib "Resistors") (part "Resistor - 1%"))
    )
    (comp (ref "R159")
      (value "43")
      (footprint "RESC1005X40N")
      (description "Resistor - 1%")
      (fields
        (field (name "MANUFACTURER PART NUMBER") "R0402_43R_1%_0.0625W_100PPM")
        (field (name "MANUFACTURER") "GENERIC")
        (field (name "AUTHOR") "CERN DEM JLC")
      )
      (libsource (lib "Resistors") (part "Resistor - 1%"))
    )
    (comp (ref "R160")
      (value "43")
      (footprint "RESC1005X40N")
      (description "Resistor - 1%")
      (fields
        (field (name "MANUFACTURER PART NUMBER") "R0402_43R_1%_0.0625W_100PPM")
        (field (name "MANUFACTURER") "GENERIC")
        (field (name "AUTHOR") "CERN DEM JLC")
      )
      (libsource (lib "Resistors") (part "Resistor - 1%"))
    )
    (comp (ref "R161")
      (value "43")
      (footprint "RESC1005X40N")
      (description "Resistor - 1%")
      (fields
        (field (name "MANUFACTURER PART NUMBER") "R0402_43R_1%_0.0625W_100PPM")
        (field (name "MANUFACTURER") "GENERIC")
        (field (name "AUTHOR") "CERN DEM JLC")
      )
      (libsource (lib "Resistors") (part "Resistor - 1%"))
    )
    (comp (ref "R162")
      (value "43")
      (footprint "RESC1005X40N")
      (description "Resistor - 1%")
      (fields
        (field (name "MANUFACTURER PART NUMBER") "R0402_43R_1%_0.0625W_100PPM")
        (field (name "MANUFACTURER") "GENERIC")
        (field (name "AUTHOR") "CERN DEM JLC")
      )
      (libsource (lib "Resistors") (part "Resistor - 1%"))
    )
    (comp (ref "R163")
      (value "43")
      (footprint "RESC1005X40N")
      (description "Resistor - 1%")
      (fields
        (field (name "MANUFACTURER PART NUMBER") "R0402_43R_1%_0.0625W_100PPM")
        (field (name "MANUFACTURER") "GENERIC")
        (field (name "AUTHOR") "CERN DEM JLC")
      )
      (libsource (lib "Resistors") (part "Resistor - 1%"))
    )
    (comp (ref "R164")
      (value "43")
      (footprint "RESC1005X40N")
      (description "Resistor - 1%")
      (fields
        (field (name "MANUFACTURER PART NUMBER") "R0402_43R_1%_0.0625W_100PPM")
        (field (name "MANUFACTURER") "GENERIC")
        (field (name "AUTHOR") "CERN DEM JLC")
      )
      (libsource (lib "Resistors") (part "Resistor - 1%"))
    )
    (comp (ref "R165")
      (value "43")
      (footprint "RESC1005X40N")
      (description "Resistor - 1%")
      (fields
        (field (name "MANUFACTURER PART NUMBER") "R0402_43R_1%_0.0625W_100PPM")
        (field (name "MANUFACTURER") "GENERIC")
        (field (name "AUTHOR") "CERN DEM JLC")
      )
      (libsource (lib "Resistors") (part "Resistor - 1%"))
    )
    (comp (ref "R166")
      (value "43")
      (footprint "RESC1005X40N")
      (description "Resistor - 1%")
      (fields
        (field (name "MANUFACTURER PART NUMBER") "R0402_43R_1%_0.0625W_100PPM")
        (field (name "MANUFACTURER") "GENERIC")
        (field (name "AUTHOR") "CERN DEM JLC")
      )
      (libsource (lib "Resistors") (part "Resistor - 1%"))
    )
    (comp (ref "R167")
      (value "43")
      (footprint "RESC1005X40N")
      (description "Resistor - 1%")
      (fields
        (field (name "MANUFACTURER PART NUMBER") "R0402_43R_1%_0.0625W_100PPM")
        (field (name "MANUFACTURER") "GENERIC")
        (field (name "AUTHOR") "CERN DEM JLC")
      )
      (libsource (lib "Resistors") (part "Resistor - 1%"))
    )
    (comp (ref "R168")
      (value "43")
      (footprint "RESC1005X40N")
      (description "Resistor - 1%")
      (fields
        (field (name "MANUFACTURER PART NUMBER") "R0402_43R_1%_0.0625W_100PPM")
        (field (name "MANUFACTURER") "GENERIC")
        (field (name "AUTHOR") "CERN DEM JLC")
      )
      (libsource (lib "Resistors") (part "Resistor - 1%"))
    )
    (comp (ref "R169")
      (value "4k7")
      (footprint "RESC1005X40N")
      (description "Resistor - 1%")
      (fields
        (field (name "MANUFACTURER PART NUMBER") "R0402_4K7_1%_0.0625W_100PPM")
        (field (name "MANUFACTURER") "GENERIC")
        (field (name "AUTHOR") "CERN DEM JLC")
      )
      (libsource (lib "Resistors") (part "Resistor - 1%"))
    )
    (comp (ref "R170")
      (value "43")
      (footprint "RESC1005X40N")
      (description "Resistor - 1%")
      (fields
        (field (name "MANUFACTURER PART NUMBER") "R0402_43R_1%_0.0625W_100PPM")
        (field (name "MANUFACTURER") "GENERIC")
        (field (name "AUTHOR") "CERN DEM JLC")
      )
      (libsource (lib "Resistors") (part "Resistor - 1%"))
    )
  )
  (nets
    (net (code "2") (name "/DDR3_32_A0") (class "Default")
      (node (ref "IC26") (pin "N3") (pinfunction "A0_N3") (pintype "input"))
      (node (ref "IC27") (pin "N3") (pinfunction "A0_N3") (pintype "input"))
      (node (ref "R164") (pin "2") (pinfunction "2_2") (pintype "passive"))
    )
    (net (code "3") (name "/DDR3_32_A1") (class "Default")
      (node (ref "IC26") (pin "P7") (pinfunction "A1_P7") (pintype "input"))
      (node (ref "IC27") (pin "P7") (pinfunction "A1_P7") (pintype "input"))
      (node (ref "R163") (pin "2") (pinfunction "2_2") (pintype "passive"))
    )
    (net (code "4") (name "/DDR3_32_A2") (class "Default")
      (node (ref "IC26") (pin "P3") (pinfunction "A2_P3") (pintype "input"))
      (node (ref "IC27") (pin "P3") (pinfunction "A2_P3") (pintype "input"))
      (node (ref "R162") (pin "2") (pinfunction "2_2") (pintype "passive"))
    )
    (net (code "5") (name "/DDR3_32_A3") (class "Default")
      (node (ref "IC26") (pin "N2") (pinfunction "A3_N2") (pintype "input"))
      (node (ref "IC27") (pin "N2") (pinfunction "A3_N2") (pintype "input"))
      (node (ref "R168") (pin "2") (pinfunction "2_2") (pintype "passive"))
    )
    (net (code "6") (name "/DDR3_32_A4") (class "Default")
      (node (ref "IC26") (pin "P8") (pinfunction "A4_P8") (pintype "input"))
      (node (ref "IC27") (pin "P8") (pinfunction "A4_P8") (pintype "input"))
      (node (ref "R167") (pin "2") (pinfunction "2_2") (pintype "passive"))
    )
    (net (code "7") (name "/DDR3_32_A5") (class "Default")
      (node (ref "IC26") (pin "P2") (pinfunction "A5_P2") (pintype "input"))
      (node (ref "IC27") (pin "P2") (pinfunction "A5_P2") (pintype "input"))
      (node (ref "R166") (pin "2") (pinfunction "2_2") (pintype "passive"))
    )
    (net (code "8") (name "/DDR3_32_A6") (class "Default")
      (node (ref "IC26") (pin "R8") (pinfunction "A6_R8") (pintype "input"))
      (node (ref "IC27") (pin "R8") (pinfunction "A6_R8") (pintype "input"))
      (node (ref "R165") (pin "2") (pinfunction "2_2") (pintype "passive"))
    )
    (net (code "9") (name "/DDR3_32_A7") (class "Default")
      (node (ref "IC26") (pin "R2") (pinfunction "A7_R2") (pintype "input"))
      (node (ref "IC27") (pin "R2") (pinfunction "A7_R2") (pintype "input"))
      (node (ref "R161") (pin "2") (pinfunction "2_2") (pintype "passive"))
    )
    (net (code "10") (name "/DDR3_32_A8") (class "Default")
      (node (ref "IC26") (pin "T8") (pinfunction "A8_T8") (pintype "input"))
      (node (ref "IC27") (pin "T8") (pinfunction "A8_T8") (pintype "input"))
      (node (ref "R160") (pin "2") (pinfunction "2_2") (pintype "passive"))
    )
    (net (code "11") (name "/DDR3_32_A9") (class "Default")
      (node (ref "IC26") (pin "R3") (pinfunction "A9_R3") (pintype "input"))
      (node (ref "IC27") (pin "R3") (pinfunction "A9_R3") (pintype "input"))
      (node (ref "R159") (pin "2") (pinfunction "2_2") (pintype "passive"))
    )
    (net (code "12") (name "/DDR3_32_A10") (class "Default")
      (node (ref "IC26") (pin "L7") (pinfunction "A10/AP_L7") (pintype "input"))
      (node (ref "IC27") (pin "L7") (pinfunction "A10/AP_L7") (pintype "input"))
      (node (ref "R158") (pin "2") (pinfunction "2_2") (pintype "passive"))
    )
    (net (code "13") (name "/DDR3_32_A11") (class "Default")
      (node (ref "IC26") (pin "R7") (pinfunction "A11_R7") (pintype "input"))
      (node (ref "IC27") (pin "R7") (pinfunction "A11_R7") (pintype "input"))
      (node (ref "R157") (pin "2") (pinfunction "2_2") (pintype "passive"))
    )
    (net (code "14") (name "/DDR3_32_A12") (class "Default")
      (node (ref "IC26") (pin "N7") (pinfunction "A12/~{BC}_N7") (pintype "input"))
      (node (ref "IC27") (pin "N7") (pinfunction "A12/~{BC}_N7") (pintype "input"))
      (node (ref "R156") (pin "2") (pinfunction "2_2") (pintype "passive"))
    )
    (net (code "15") (name "/DDR3_32_A13") (class "Default")
      (node (ref "IC26") (pin "T3") (pinfunction "A13_T3") (pintype "input"))
      (node (ref "IC27") (pin "T3") (pinfunction "A13_T3") (pintype "input"))
      (node (ref "R155") (pin "2") (pinfunction "2_2") (pintype "passive"))
    )
    (net (code "16") (name "/DDR3_32_A14") (class "Default")
      (node (ref "IC26") (pin "T7") (pinfunction "A14_T7") (pintype "passive"))
      (node (ref "IC27") (pin "T7") (pinfunction "A14_T7") (pintype "passive"))
      (node (ref "R170") (pin "2") (pinfunction "2_2") (pintype "passive"))
    )
    (net (code "18") (name "/DDR3_32_BA0") (class "Default")
      (node (ref "IC26") (pin "M2") (pinfunction "BA0_M2") (pintype "input"))
      (node (ref "IC27") (pin "M2") (pinfunction "BA0_M2") (pintype "input"))
      (node (ref "R146") (pin "2") (pinfunction "2_2") (pintype "passive"))
    )
    (net (code "19") (name "/DDR3_32_BA1") (class "Default")
      (node (ref "IC26") (pin "N8") (pinfunction "BA1_N8") (pintype "input"))
      (node (ref "IC27") (pin "N8") (pinfunction "BA1_N8") (pintype "input"))
      (node (ref "R145") (pin "2") (pinfunction "2_2") (pintype "passive"))
    )
    (net (code "20") (name "/DDR3_32_BA2") (class "Default")
      (node (ref "IC26") (pin "M3") (pinfunction "BA2_M3") (pintype "input"))
      (node (ref "IC27") (pin "M3") (pinfunction "BA2_M3") (pintype "input"))
      (node (ref "R144") (pin "2") (pinfunction "2_2") (pintype "passive"))
    )
    (net (code "21") (name "/DDR3_32_CAS_N") (class "Default")
      (node (ref "IC26") (pin "K3") (pinfunction "~{CAS}_K3") (pintype "input"))
      (node (ref "IC27") (pin "K3") (pinfunction "~{CAS}_K3") (pintype "input"))
      (node (ref "R150") (pin "2") (pinfunction "2_2") (pintype "passive"))
    )
    (net (code "22") (name "/DDR3_32_CKE") (class "Default")
      (node (ref "IC26") (pin "K9") (pinfunction "CKE_K9") (pintype "input"))
      (node (ref "IC27") (pin "K9") (pinfunction "CKE_K9") (pintype "input"))
      (node (ref "R152") (pin "2") (pinfunction "2_2") (pintype "passive"))
    )
    (net (code "23") (name "/DDR3_32_CK_N") (class "Default")
      (node (ref "IC26") (pin "K7") (pinfunction "~{CK}_K7") (pintype "input"))
      (node (ref "IC27") (pin "K7") (pinfunction "~{CK}_K7") (pintype "input"))
      (node (ref "R153") (pin "2") (pinfunction "2_2") (pintype "passive"))
    )
    (net (code "24") (name "/DDR3_32_CK_P") (class "Default")
      (node (ref "IC26") (pin "J7") (pinfunction "CK_J7") (pintype "input"))
      (node (ref "IC27") (pin "J7") (pinfunction "CK_J7") (pintype "input"))
      (node (ref "R154") (pin "2") (pinfunction "2_2") (pintype "passive"))
    )
    (net (code "25") (name "/DDR3_32_CS_N") (class "Default")
      (node (ref "IC26") (pin "L2") (pinfunction "~{CS}_L2") (pintype "input"))
      (node (ref "IC27") (pin "L2") (pinfunction "~{CS}_L2") (pintype "input"))
      (node (ref "R149") (pin "2") (pinfunction "2_2") (pintype "passive"))
    )
    (net (code "26") (name "/DDR3_32_DM0") (class "Default")
      (node (ref "IC26") (pin "E7") (pinfunction "LDM_E7") (pintype "input"))
    )
    (net (code "27") (name "/DDR3_32_DM1") (class "Default")
      (node (ref "IC26") (pin "D3") (pinfunction "UDM_D3") (pintype "input"))
    )
    (net (code "28") (name "/DDR3_32_DM2") (class "Default")
      (node (ref "IC27") (pin "E7") (pinfunction "LDM_E7") (pintype "input"))
    )
    (net (code "29") (name "/DDR3_32_DM3") (class "Default")
      (node (ref "IC27") (pin "D3") (pinfunction "UDM_D3") (pintype "input"))
    )
    (net (code "31") (name "/DDR3_32_DQ0") (class "Default")
      (node (ref "IC26") (pin "E3") (pinfunction "DQ0_E3") (pintype "bidirectional"))
    )
    (net (code "32") (name "/DDR3_32_DQ1") (class "Default")
      (node (ref "IC26") (pin "F7") (pinfunction "DQ1_F7") (pintype "bidirectional"))
    )
    (net (code "33") (name "/DDR3_32_DQ2") (class "Default")
      (node (ref "IC26") (pin "F2") (pinfunction "DQ2_F2") (pintype "bidirectional"))
    )
    (net (code "34") (name "/DDR3_32_DQ3") (class "Default")
      (node (ref "IC26") (pin "F8") (pinfunction "DQ3_F8") (pintype "bidirectional"))
    )
    (net (code "35") (name "/DDR3_32_DQ4") (class "Default")
      (node (ref "IC26") (pin "H3") (pinfunction "DQ4_H3") (pintype "bidirectional"))
    )
    (net (code "36") (name "/DDR3_32_DQ5") (class "Default")
      (node (ref "IC26") (pin "H8") (pinfunction "DQ5_H8") (pintype "bidirectional"))
    )
    (net (code "37") (name "/DDR3_32_DQ6") (class "Default")
      (node (ref "IC26") (pin "G2") (pinfunction "DQ6_G2") (pintype "bidirectional"))
    )
    (net (code "38") (name "/DDR3_32_DQ7") (class "Default")
      (node (ref "IC26") (pin "H7") (pinfunction "DQ7_H7") (pintype "bidirectional"))
    )
    (net (code "39") (name "/DDR3_32_DQ8") (class "Default")
      (node (ref "IC26") (pin "D7") (pinfunction "DQ8_D7") (pintype "bidirectional"))
    )
    (net (code "40") (name "/DDR3_32_DQ9") (class "Default")
      (node (ref "IC26") (pin "C3") (pinfunction "DQ9_C3") (pintype "bidirectional"))
    )
    (net (code "41") (name "/DDR3_32_DQ10") (class "Default")
      (node (ref "IC26") (pin "C8") (pinfunction "DQ10_C8") (pintype "bidirectional"))
    )
    (net (code "42") (name "/DDR3_32_DQ11") (class "Default")
      (node (ref "IC26") (pin "C2") (pinfunction "DQ11_C2") (pintype "bidirectional"))
    )
    (net (code "43") (name "/DDR3_32_DQ12") (class "Default")
      (node (ref "IC26") (pin "A7") (pinfunction "DQ12_A7") (pintype "bidirectional"))
    )
    (net (code "44") (name "/DDR3_32_DQ13") (class "Default")
      (node (ref "IC26") (pin "A2") (pinfunction "DQ13_A2") (pintype "bidirectional"))
    )
    (net (code "45") (name "/DDR3_32_DQ14") (class "Default")
      (node (ref "IC26") (pin "B8") (pinfunction "DQ14_B8") (pintype "bidirectional"))
    )
    (net (code "46") (name "/DDR3_32_DQ15") (class "Default")
      (node (ref "IC26") (pin "A3") (pinfunction "DQ15_A3") (pintype "bidirectional"))
    )
    (net (code "47") (name "/DDR3_32_DQ16") (class "Default")
      (node (ref "IC27") (pin "E3") (pinfunction "DQ0_E3") (pintype "bidirectional"))
    )
    (net (code "48") (name "/DDR3_32_DQ17") (class "Default")
      (node (ref "IC27") (pin "F7") (pinfunction "DQ1_F7") (pintype "bidirectional"))
    )
    (net (code "49") (name "/DDR3_32_DQ18") (class "Default")
      (node (ref "IC27") (pin "F2") (pinfunction "DQ2_F2") (pintype "bidirectional"))
    )
    (net (code "50") (name "/DDR3_32_DQ19") (class "Default")
      (node (ref "IC27") (pin "F8") (pinfunction "DQ3_F8") (pintype "bidirectional"))
    )
    (net (code "51") (name "/DDR3_32_DQ20") (class "Default")
      (node (ref "IC27") (pin "H3") (pinfunction "DQ4_H3") (pintype "bidirectional"))
    )
    (net (code "52") (name "/DDR3_32_DQ21") (class "Default")
      (node (ref "IC27") (pin "H8") (pinfunction "DQ5_H8") (pintype "bidirectional"))
    )
    (net (code "53") (name "/DDR3_32_DQ22") (class "Default")
      (node (ref "IC27") (pin "G2") (pinfunction "DQ6_G2") (pintype "bidirectional"))
    )
    (net (code "54") (name "/DDR3_32_DQ23") (class "Default")
      (node (ref "IC27") (pin "H7") (pinfunction "DQ7_H7") (pintype "bidirectional"))
    )
    (net (code "55") (name "/DDR3_32_DQ24") (class "Default")
      (node (ref "IC27") (pin "D7") (pinfunction "DQ8_D7") (pintype "bidirectional"))
    )
    (net (code "56") (name "/DDR3_32_DQ25") (class "Default")
      (node (ref "IC27") (pin "C3") (pinfunction "DQ9_C3") (pintype "bidirectional"))
    )
    (net (code "57") (name "/DDR3_32_DQ26") (class "Default")
      (node (ref "IC27") (pin "C8") (pinfunction "DQ10_C8") (pintype "bidirectional"))
    )
    (net (code "58") (name "/DDR3_32_DQ27") (class "Default")
      (node (ref "IC27") (pin "C2") (pinfunction "DQ11_C2") (pintype "bidirectional"))
    )
    (net (code "59") (name "/DDR3_32_DQ28") (class "Default")
      (node (ref "IC27") (pin "A7") (pinfunction "DQ12_A7") (pintype "bidirectional"))
    )
    (net (code "60") (name "/DDR3_32_DQ29") (class "Default")
      (node (ref "IC27") (pin "A2") (pinfunction "DQ13_A2") (pintype "bidirectional"))
    )
    (net (code "61") (name "/DDR3_32_DQ30") (class "Default")
      (node (ref "IC27") (pin "B8") (pinfunction "DQ14_B8") (pintype "bidirectional"))
    )
    (net (code "62") (name "/DDR3_32_DQ31") (class "Default")
      (node (ref "IC27") (pin "A3") (pinfunction "DQ15_A3") (pintype "bidirectional"))
    )
    (net (code "63") (name "/DDR3_32_DQS0_N") (class "Default")
      (node (ref "IC26") (pin "G3") (pinfunction "~{LDQS}_G3") (pintype "bidirectional"))
    )
    (net (code "64") (name "/DDR3_32_DQS0_P") (class "Default")
      (node (ref "IC26") (pin "F3") (pinfunction "LDQS_F3") (pintype "bidirectional"))
    )
    (net (code "65") (name "/DDR3_32_DQS1_N") (class "Default")
      (node (ref "IC26") (pin "B7") (pinfunction "~{UDQS}_B7") (pintype "bidirectional"))
    )
    (net (code "66") (name "/DDR3_32_DQS1_P") (class "Default")
      (node (ref "IC26") (pin "C7") (pinfunction "UDQS_C7") (pintype "bidirectional"))
    )
    (net (code "67") (name "/DDR3_32_DQS2_N") (class "Default")
      (node (ref "IC27") (pin "G3") (pinfunction "~{LDQS}_G3") (pintype "bidirectional"))
    )
    (net (code "68") (name "/DDR3_32_DQS2_P") (class "Default")
      (node (ref "IC27") (pin "F3") (pinfunction "LDQS_F3") (pintype "bidirectional"))
    )
    (net (code "69") (name "/DDR3_32_DQS3_N") (class "Default")
      (node (ref "IC27") (pin "B7") (pinfunction "~{UDQS}_B7") (pintype "bidirectional"))
    )
    (net (code "70") (name "/DDR3_32_DQS3_P") (class "Default")
      (node (ref "IC27") (pin "C7") (pinfunction "UDQS_C7") (pintype "bidirectional"))
    )
    (net (code "72") (name "/DDR3_32_ODT") (class "Default")
      (node (ref "IC26") (pin "K1") (pinfunction "ODT_K1") (pintype "input"))
      (node (ref "IC27") (pin "K1") (pinfunction "ODT_K1") (pintype "input"))
      (node (ref "R147") (pin "2") (pinfunction "2_2") (pintype "passive"))
    )
    (net (code "73") (name "/DDR3_32_RAS_N") (class "Default")
      (node (ref "IC26") (pin "J3") (pinfunction "~{RAS}_J3") (pintype "input"))
      (node (ref "IC27") (pin "J3") (pinfunction "~{RAS}_J3") (pintype "input"))
      (node (ref "R151") (pin "2") (pinfunction "2_2") (pintype "passive"))
    )
    (net (code "74") (name "/DDR3_32_RST_N") (class "Default")
      (node (ref "IC26") (pin "T2") (pinfunction "~{RESET}_T2") (pintype "input"))
      (node (ref "IC27") (pin "T2") (pinfunction "~{RESET}_T2") (pintype "input"))
      (node (ref "R169") (pin "2") (pinfunction "2_2") (pintype "passive"))
    )
    (net (code "75") (name "/DDR3_32_WE_N") (class "Default")
      (node (ref "IC26") (pin "L3") (pinfunction "~{WE}_L3") (pintype "input"))
      (node (ref "IC27") (pin "L3") (pinfunction "~{WE}_L3") (pintype "input"))
      (node (ref "R148") (pin "2") (pinfunction "2_2") (pintype "passive"))
    )
    (net (code "76") (name "/DDR32_VREF") (class "Default")
      (node (ref "C148") (pin "1") (pinfunction "1_1") (pintype "passive"))
      (node (ref "C149") (pin "1") (pinfunction "1_1") (pintype "passive"))
      (node (ref "C151") (pin "1") (pinfunction "1_1") (pintype "passive"))
      (node (ref "C152") (pin "1") (pinfunction "1_1") (pintype "passive"))
      (node (ref "C153") (pin "2") (pinfunction "2_2") (pintype "passive"))
      (node (ref "IC26") (pin "H1") (pinfunction "VREFDQ_H1") (pintype "power_in"))
      (node (ref "IC26") (pin "M8") (pinfunction "VREFCA_M8") (pintype "power_in"))
      (node (ref "IC27") (pin "H1") (pinfunction "VREFDQ_H1") (pintype "power_in"))
      (node (ref "IC27") (pin "M8") (pinfunction "VREFCA_M8") (pintype "power_in"))
      (node (ref "IC29") (pin "6") (pinfunction "REFOUT_6") (pintype "output"))
    )
    (net (code "77") (name "/PGOOD") (class "Default")
      (node (ref "IC29") (pin "9") (pinfunction "PGOOD_9") (pintype "output"))
    )
    (net (code "79") (name "/VOSNS1") (class "Default")
      (node (ref "C437") (pin "2") (pinfunction "2_2") (pintype "passive"))
      (node (ref "IC29") (pin "5") (pinfunction "VOSNS_5") (pintype "input"))
      (node (ref "R141") (pin "1") (pinfunction "1_1") (pintype "passive"))
    )
    (net (code "80") (name "/ZQ5") (class "Default")
      (node (ref "IC26") (pin "L8") (pinfunction "ZQ_L8") (pintype "input"))
      (node (ref "R143") (pin "2") (pinfunction "2_2") (pintype "passive"))
    )
    (net (code "81") (name "/ZQ6") (class "Default")
      (node (ref "IC27") (pin "L8") (pinfunction "ZQ_L8") (pintype "input"))
      (node (ref "R142") (pin "2") (pinfunction "2_2") (pintype "passive"))
    )
    (net (code "83") (name "GND") (class "Default")
      (node (ref "C113") (pin "2") (pinfunction "2_2") (pintype "passive"))
      (node (ref "C114") (pin "2") (pinfunction "2_2") (pintype "passive"))
      (node (ref "C115") (pin "2") (pinfunction "2_2") (pintype "passive"))
      (node (ref "C116") (pin "2") (pinfunction "2_2") (pintype "passive"))
      (node (ref "C117") (pin "2") (pinfunction "2_2") (pintype "passive"))
      (node (ref "C118") (pin "2") (pinfunction "2_2") (pintype "passive"))
      (node (ref "C119") (pin "2") (pinfunction "2_2") (pintype "passive"))
      (node (ref "C120") (pin "2") (pinfunction "2_2") (pintype "passive"))
      (node (ref "C121") (pin "2") (pinfunction "2_2") (pintype "passive"))
      (node (ref "C122") (pin "2") (pinfunction "2_2") (pintype "passive"))
      (node (ref "C123") (pin "2") (pinfunction "2_2") (pintype "passive"))
      (node (ref "C124") (pin "2") (pinfunction "2_2") (pintype "passive"))
      (node (ref "C125") (pin "2") (pinfunction "2_2") (pintype "passive"))
      (node (ref "C126") (pin "2") (pinfunction "2_2") (pintype "passive"))
      (node (ref "C127") (pin "2") (pinfunction "2_2") (pintype "passive"))
      (node (ref "C128") (pin "2") (pinfunction "2_2") (pintype "passive"))
      (node (ref "C129") (pin "2") (pinfunction "2_2") (pintype "passive"))
      (node (ref "C130") (pin "2") (pinfunction "2_2") (pintype "passive"))
      (node (ref "C131") (pin "2") (pinfunction "2_2") (pintype "passive"))
      (node (ref "C132") (pin "2") (pinfunction "2_2") (pintype "passive"))
      (node (ref "C133") (pin "2") (pinfunction "2_2") (pintype "passive"))
      (node (ref "C134") (pin "2") (pinfunction "2_2") (pintype "passive"))
      (node (ref "C135") (pin "2") (pinfunction "2_2") (pintype "passive"))
      (node (ref "C136") (pin "2") (pinfunction "2_2") (pintype "passive"))
      (node (ref "C137") (pin "2") (pinfunction "2_2") (pintype "passive"))
      (node (ref "C138") (pin "2") (pinfunction "2_2") (pintype "passive"))
      (node (ref "C139") (pin "2") (pinfunction "2_2") (pintype "passive"))
      (node (ref "C140") (pin "2") (pinfunction "2_2") (pintype "passive"))
      (node (ref "C141") (pin "2") (pinfunction "2_2") (pintype "passive"))
      (node (ref "C142") (pin "2") (pinfunction "2_2") (pintype "passive"))
      (node (ref "C143") (pin "2") (pinfunction "2_2") (pintype "passive"))
      (node (ref "C144") (pin "2") (pinfunction "2_2") (pintype "passive"))
      (node (ref "C145") (pin "2") (pinfunction "2_2") (pintype "passive"))
      (node (ref "C146") (pin "2") (pinfunction "2_2") (pintype "passive"))
      (node (ref "C147") (pin "2") (pinfunction "2_2") (pintype "passive"))
      (node (ref "C148") (pin "2") (pinfunction "2_2") (pintype "passive"))
      (node (ref "C149") (pin "2") (pinfunction "2_2") (pintype "passive"))
      (node (ref "C150") (pin "1") (pinfunction "1_1") (pintype "passive"))
      (node (ref "C151") (pin "2") (pinfunction "2_2") (pintype "passive"))
      (node (ref "C152") (pin "2") (pinfunction "2_2") (pintype "passive"))
      (node (ref "C153") (pin "1") (pinfunction "1_1") (pintype "passive"))
      (node (ref "C437") (pin "1") (pinfunction "1_1") (pintype "passive"))
      (node (ref "C438") (pin "1") (pinfunction "1_1") (pintype "passive"))
      (node (ref "C439") (pin "2") (pinfunction "2_2") (pintype "passive"))
      (node (ref "C440") (pin "2") (pinfunction "2_2") (pintype "passive"))
      (node (ref "C441") (pin "2") (pinfunction "2_2") (pintype "passive"))
      (node (ref "C442") (pin "2") (pinfunction "2_2") (pintype "passive"))
      (node (ref "C443") (pin "2") (pinfunction "2_2") (pintype "passive"))
      (node (ref "C444") (pin "2") (pinfunction "2_2") (pintype "passive"))
      (node (ref "C445") (pin "2") (pinfunction "2_2") (pintype "passive"))
      (node (ref "C637") (pin "1") (pinfunction "1_1") (pintype "passive"))
      (node (ref "C638") (pin "1") (pinfunction "1_1") (pintype "passive"))
      (node (ref "IC26") (pin "A9") (pinfunction "VSS_A9") (pintype "power_in"))
      (node (ref "IC26") (pin "B1") (pinfunction "VSSQ_B1") (pintype "power_in"))
      (node (ref "IC26") (pin "B3") (pinfunction "VSS_B3") (pintype "power_in"))
      (node (ref "IC26") (pin "B9") (pinfunction "VSSQ_B9") (pintype "power_in"))
      (node (ref "IC26") (pin "D1") (pinfunction "VSSQ_D1") (pintype "power_in"))
      (node (ref "IC26") (pin "D8") (pinfunction "VSSQ_D8") (pintype "power_in"))
      (node (ref "IC26") (pin "E1") (pinfunction "VSS_E1") (pintype "power_in"))
      (node (ref "IC26") (pin "E2") (pinfunction "VSSQ_E2") (pintype "power_in"))
      (node (ref "IC26") (pin "E8") (pinfunction "VSSQ_E8") (pintype "power_in"))
      (node (ref "IC26") (pin "F9") (pinfunction "VSSQ_F9") (pintype "power_in"))
      (node (ref "IC26") (pin "G1") (pinfunction "VSSQ_G1") (pintype "power_in"))
      (node (ref "IC26") (pin "G8") (pinfunction "VSS_G8") (pintype "power_in"))
      (node (ref "IC26") (pin "G9") (pinfunction "VSSQ_G9") (pintype "power_in"))
      (node (ref "IC26") (pin "J2") (pinfunction "VSS_J2") (pintype "power_in"))
      (node (ref "IC26") (pin "J8") (pinfunction "VSS_J8") (pintype "power_in"))
      (node (ref "IC26") (pin "M1") (pinfunction "VSS_M1") (pintype "power_in"))
      (node (ref "IC26") (pin "M9") (pinfunction "VSS_M9") (pintype "power_in"))
      (node (ref "IC26") (pin "P1") (pinfunction "VSS_P1") (pintype "power_in"))
      (node (ref "IC26") (pin "P9") (pinfunction "VSS_P9") (pintype "power_in"))
      (node (ref "IC26") (pin "T1") (pinfunction "VSS_T1") (pintype "power_in"))
      (node (ref "IC26") (pin "T9") (pinfunction "VSS_T9") (pintype "power_in"))
      (node (ref "IC27") (pin "A9") (pinfunction "VSS_A9") (pintype "power_in"))
      (node (ref "IC27") (pin "B1") (pinfunction "VSSQ_B1") (pintype "power_in"))
      (node (ref "IC27") (pin "B3") (pinfunction "VSS_B3") (pintype "power_in"))
      (node (ref "IC27") (pin "B9") (pinfunction "VSSQ_B9") (pintype "power_in"))
      (node (ref "IC27") (pin "D1") (pinfunction "VSSQ_D1") (pintype "power_in"))
      (node (ref "IC27") (pin "D8") (pinfunction "VSSQ_D8") (pintype "power_in"))
      (node (ref "IC27") (pin "E1") (pinfunction "VSS_E1") (pintype "power_in"))
      (node (ref "IC27") (pin "E2") (pinfunction "VSSQ_E2") (pintype "power_in"))
      (node (ref "IC27") (pin "E8") (pinfunction "VSSQ_E8") (pintype "power_in"))
      (node (ref "IC27") (pin "F9") (pinfunction "VSSQ_F9") (pintype "power_in"))
      (node (ref "IC27") (pin "G1") (pinfunction "VSSQ_G1") (pintype "power_in"))
      (node (ref "IC27") (pin "G8") (pinfunction "VSS_G8") (pintype "power_in"))
      (node (ref "IC27") (pin "G9") (pinfunction "VSSQ_G9") (pintype "power_in"))
      (node (ref "IC27") (pin "J2") (pinfunction "VSS_J2") (pintype "power_in"))
      (node (ref "IC27") (pin "J8") (pinfunction "VSS_J8") (pintype "power_in"))
      (node (ref "IC27") (pin "M1") (pinfunction "VSS_M1") (pintype "power_in"))
      (node (ref "IC27") (pin "M9") (pinfunction "VSS_M9") (pintype "power_in"))
      (node (ref "IC27") (pin "P1") (pinfunction "VSS_P1") (pintype "power_in"))
      (node (ref "IC27") (pin "P9") (pinfunction "VSS_P9") (pintype "power_in"))
      (node (ref "IC27") (pin "T1") (pinfunction "VSS_T1") (pintype "power_in"))
      (node (ref "IC27") (pin "T9") (pinfunction "VSS_T9") (pintype "power_in"))
      (node (ref "IC29") (pin "11") (pinfunction "EP_11") (pintype "power_in"))
      (node (ref "IC29") (pin "4") (pinfunction "PGND_4") (pintype "power_in"))
      (node (ref "IC29") (pin "8") (pinfunction "GND_8") (pintype "power_in"))
      (node (ref "R140") (pin "1") (pinfunction "1_1") (pintype "passive"))
      (node (ref "R142") (pin "1") (pinfunction "1_1") (pintype "passive"))
      (node (ref "R143") (pin "1") (pinfunction "1_1") (pintype "passive"))
      (node (ref "R169") (pin "1") (pinfunction "1_1") (pintype "passive"))
    )
    (net (code "84") (name "Net-(IC29-REFIN)") (class "Default")
      (node (ref "C438") (pin "2") (pinfunction "2_2") (pintype "passive"))
      (node (ref "IC29") (pin "1") (pinfunction "REFIN_1") (pintype "input"))
      (node (ref "R139") (pin "2") (pinfunction "2_2") (pintype "passive"))
      (node (ref "R140") (pin "2") (pinfunction "2_2") (pintype "passive"))
    )
    (net (code "85") (name "P1V5") (class "Default")
      (node (ref "C125") (pin "1") (pinfunction "1_1") (pintype "passive"))
      (node (ref "C126") (pin "1") (pinfunction "1_1") (pintype "passive"))
      (node (ref "C127") (pin "1") (pinfunction "1_1") (pintype "passive"))
      (node (ref "C128") (pin "1") (pinfunction "1_1") (pintype "passive"))
      (node (ref "C129") (pin "1") (pinfunction "1_1") (pintype "passive"))
      (node (ref "C130") (pin "1") (pinfunction "1_1") (pintype "passive"))
      (node (ref "C131") (pin "1") (pinfunction "1_1") (pintype "passive"))
      (node (ref "C132") (pin "1") (pinfunction "1_1") (pintype "passive"))
      (node (ref "C133") (pin "1") (pinfunction "1_1") (pintype "passive"))
      (node (ref "C134") (pin "1") (pinfunction "1_1") (pintype "passive"))
      (node (ref "C135") (pin "1") (pinfunction "1_1") (pintype "passive"))
      (node (ref "C136") (pin "1") (pinfunction "1_1") (pintype "passive"))
      (node (ref "C137") (pin "1") (pinfunction "1_1") (pintype "passive"))
      (node (ref "C138") (pin "1") (pinfunction "1_1") (pintype "passive"))
      (node (ref "C139") (pin "1") (pinfunction "1_1") (pintype "passive"))
      (node (ref "C140") (pin "1") (pinfunction "1_1") (pintype "passive"))
      (node (ref "C141") (pin "1") (pinfunction "1_1") (pintype "passive"))
      (node (ref "C142") (pin "1") (pinfunction "1_1") (pintype "passive"))
      (node (ref "C143") (pin "1") (pinfunction "1_1") (pintype "passive"))
      (node (ref "C144") (pin "1") (pinfunction "1_1") (pintype "passive"))
      (node (ref "C145") (pin "1") (pinfunction "1_1") (pintype "passive"))
      (node (ref "C146") (pin "1") (pinfunction "1_1") (pintype "passive"))
      (node (ref "C147") (pin "1") (pinfunction "1_1") (pintype "passive"))
      (node (ref "C150") (pin "2") (pinfunction "2_2") (pintype "passive"))
      (node (ref "C440") (pin "1") (pinfunction "1_1") (pintype "passive"))
      (node (ref "C441") (pin "1") (pinfunction "1_1") (pintype "passive"))
      (node (ref "C442") (pin "1") (pinfunction "1_1") (pintype "passive"))
      (node (ref "C443") (pin "1") (pinfunction "1_1") (pintype "passive"))
      (node (ref "C445") (pin "1") (pinfunction "1_1") (pintype "passive"))
      (node (ref "IC26") (pin "A1") (pinfunction "VDDQ_A1") (pintype "power_in"))
      (node (ref "IC26") (pin "A8") (pinfunction "VDDQ_A8") (pintype "power_in"))
      (node (ref "IC26") (pin "B2") (pinfunction "VDD_B2") (pintype "power_in"))
      (node (ref "IC26") (pin "C1") (pinfunction "VDDQ_C1") (pintype "power_in"))
      (node (ref "IC26") (pin "C9") (pinfunction "VDDQ_C9") (pintype "power_in"))
      (node (ref "IC26") (pin "D2") (pinfunction "VDDQ_D2") (pintype "power_in"))
      (node (ref "IC26") (pin "D9") (pinfunction "VDD_D9") (pintype "power_in"))
      (node (ref "IC26") (pin "E9") (pinfunction "VDDQ_E9") (pintype "power_in"))
      (node (ref "IC26") (pin "F1") (pinfunction "VDDQ_F1") (pintype "power_in"))
      (node (ref "IC26") (pin "G7") (pinfunction "VDD_G7") (pintype "power_in"))
      (node (ref "IC26") (pin "H2") (pinfunction "VDDQ_H2") (pintype "power_in"))
      (node (ref "IC26") (pin "H9") (pinfunction "VDDQ_H9") (pintype "power_in"))
      (node (ref "IC26") (pin "K2") (pinfunction "VDD_K2") (pintype "power_in"))
      (node (ref "IC26") (pin "K8") (pinfunction "VDD_K8") (pintype "power_in"))
      (node (ref "IC26") (pin "N1") (pinfunction "VDD_N1") (pintype "power_in"))
      (node (ref "IC26") (pin "N9") (pinfunction "VDD_N9") (pintype "power_in"))
      (node (ref "IC26") (pin "R1") (pinfunction "VDD_R1") (pintype "power_in"))
      (node (ref "IC26") (pin "R9") (pinfunction "VDD_R9") (pintype "power_in"))
      (node (ref "IC27") (pin "A1") (pinfunction "VDDQ_A1") (pintype "power_in"))
      (node (ref "IC27") (pin "A8") (pinfunction "VDDQ_A8") (pintype "power_in"))
      (node (ref "IC27") (pin "B2") (pinfunction "VDD_B2") (pintype "power_in"))
      (node (ref "IC27") (pin "C1") (pinfunction "VDDQ_C1") (pintype "power_in"))
      (node (ref "IC27") (pin "C9") (pinfunction "VDDQ_C9") (pintype "power_in"))
      (node (ref "IC27") (pin "D2") (pinfunction "VDDQ_D2") (pintype "power_in"))
      (node (ref "IC27") (pin "D9") (pinfunction "VDD_D9") (pintype "power_in"))
      (node (ref "IC27") (pin "E9") (pinfunction "VDDQ_E9") (pintype "power_in"))
      (node (ref "IC27") (pin "F1") (pinfunction "VDDQ_F1") (pintype "power_in"))
      (node (ref "IC27") (pin "G7") (pinfunction "VDD_G7") (pintype "power_in"))
      (node (ref "IC27") (pin "H2") (pinfunction "VDDQ_H2") (pintype "power_in"))
      (node (ref "IC27") (pin "H9") (pinfunction "VDDQ_H9") (pintype "power_in"))
      (node (ref "IC27") (pin "K2") (pinfunction "VDD_K2") (pintype "power_in"))
      (node (ref "IC27") (pin "K8") (pinfunction "VDD_K8") (pintype "power_in"))
      (node (ref "IC27") (pin "N1") (pinfunction "VDD_N1") (pintype "power_in"))
      (node (ref "IC27") (pin "N9") (pinfunction "VDD_N9") (pintype "power_in"))
      (node (ref "IC27") (pin "R1") (pinfunction "VDD_R1") (pintype "power_in"))
      (node (ref "IC27") (pin "R9") (pinfunction "VDD_R9") (pintype "power_in"))
      (node (ref "IC29") (pin "2") (pinfunction "VLDOIN_2") (pintype "input"))
      (node (ref "R139") (pin "1") (pinfunction "1_1") (pintype "passive"))
    )
    (net (code "86") (name "P3V3") (class "Default")
      (node (ref "C444") (pin "1") (pinfunction "1_1") (pintype "passive"))
      (node (ref "IC29") (pin "10") (pinfunction "VIN_10") (pintype "input"))
      (node (ref "IC29") (pin "7") (pinfunction "EN_7") (pintype "input"))
    )
    (net (code "87") (name "VTT32") (class "Default")
      (node (ref "C113") (pin "1") (pinfunction "1_1") (pintype "passive"))
      (node (ref "C114") (pin "1") (pinfunction "1_1") (pintype "passive"))
      (node (ref "C115") (pin "1") (pinfunction "1_1") (pintype "passive"))
      (node (ref "C116") (pin "1") (pinfunction "1_1") (pintype "passive"))
      (node (ref "C117") (pin "1") (pinfunction "1_1") (pintype "passive"))
      (node (ref "C118") (pin "1") (pinfunction "1_1") (pintype "passive"))
      (node (ref "C119") (pin "1") (pinfunction "1_1") (pintype "passive"))
      (node (ref "C120") (pin "1") (pinfunction "1_1") (pintype "passive"))
      (node (ref "C121") (pin "1") (pinfunction "1_1") (pintype "passive"))
      (node (ref "C122") (pin "1") (pinfunction "1_1") (pintype "passive"))
      (node (ref "C123") (pin "1") (pinfunction "1_1") (pintype "passive"))
      (node (ref "C124") (pin "1") (pinfunction "1_1") (pintype "passive"))
      (node (ref "C439") (pin "1") (pinfunction "1_1") (pintype "passive"))
      (node (ref "C637") (pin "2") (pinfunction "2_2") (pintype "passive"))
      (node (ref "C638") (pin "2") (pinfunction "2_2") (pintype "passive"))
      (node (ref "IC29") (pin "3") (pinfunction "VO_3") (pintype "power_in"))
      (node (ref "R141") (pin "2") (pinfunction "2_2") (pintype "passive"))
      (node (ref "R144") (pin "1") (pinfunction "1_1") (pintype "passive"))
      (node (ref "R145") (pin "1") (pinfunction "1_1") (pintype "passive"))
      (node (ref "R146") (pin "1") (pinfunction "1_1") (pintype "passive"))
      (node (ref "R147") (pin "1") (pinfunction "1_1") (pintype "passive"))
      (node (ref "R148") (pin "1") (pinfunction "1_1") (pintype "passive"))
      (node (ref "R149") (pin "1") (pinfunction "1_1") (pintype "passive"))
      (node (ref "R150") (pin "1") (pinfunction "1_1") (pintype "passive"))
      (node (ref "R151") (pin "1") (pinfunction "1_1") (pintype "passive"))
      (node (ref "R152") (pin "1") (pinfunction "1_1") (pintype "passive"))
      (node (ref "R153") (pin "1") (pinfunction "1_1") (pintype "passive"))
      (node (ref "R154") (pin "1") (pinfunction "1_1") (pintype "passive"))
      (node (ref "R155") (pin "1") (pinfunction "1_1") (pintype "passive"))
      (node (ref "R156") (pin "1") (pinfunction "1_1") (pintype "passive"))
      (node (ref "R157") (pin "1") (pinfunction "1_1") (pintype "passive"))
      (node (ref "R158") (pin "1") (pinfunction "1_1") (pintype "passive"))
      (node (ref "R159") (pin "1") (pinfunction "1_1") (pintype "passive"))
      (node (ref "R160") (pin "1") (pinfunction "1_1") (pintype "passive"))
      (node (ref "R161") (pin "1") (pinfunction "1_1") (pintype "passive"))
      (node (ref "R162") (pin "1") (pinfunction "1_1") (pintype "passive"))
      (node (ref "R163") (pin "1") (pinfunction "1_1") (pintype "passive"))
      (node (ref "R164") (pin "1") (pinfunction "1_1") (pintype "passive"))
      (node (ref "R165") (pin "1") (pinfunction "1_1") (pintype "passive"))
      (node (ref "R166") (pin "1") (pinfunction "1_1") (pintype "passive"))
      (node (ref "R167") (pin "1") (pinfunction "1_1") (pintype "passive"))
      (node (ref "R168") (pin "1") (pinfunction "1_1") (pintype "passive"))
      (node (ref "R170") (pin "1") (pinfunction "1_1") (pintype "passive"))
    )
    (net (code "88") (name "unconnected-(IC26-NC-PadJ1)") (class "Default")
      (node (ref "IC26") (pin "J1") (pinfunction "NC_J1") (pintype "passive"))
    )
    (net (code "89") (name "unconnected-(IC26-NC-PadJ9)") (class "Default")
      (node (ref "IC26") (pin "J9") (pinfunction "NC_J9") (pintype "passive"))
    )
    (net (code "90") (name "unconnected-(IC26-NC-PadL1)") (class "Default")
      (node (ref "IC26") (pin "L1") (pinfunction "NC_L1") (pintype "passive"))
    )
    (net (code "91") (name "unconnected-(IC26-NC-PadL9)") (class "Default")
      (node (ref "IC26") (pin "L9") (pinfunction "NC_L9") (pintype "passive"))
    )
    (net (code "92") (name "unconnected-(IC26-NC-PadM7)") (class "Default")
      (node (ref "IC26") (pin "M7") (pinfunction "NC_M7") (pintype "passive"))
    )
    (net (code "93") (name "unconnected-(IC27-NC-PadJ1)") (class "Default")
      (node (ref "IC27") (pin "J1") (pinfunction "NC_J1") (pintype "passive"))
    )
    (net (code "94") (name "unconnected-(IC27-NC-PadJ9)") (class "Default")
      (node (ref "IC27") (pin "J9") (pinfunction "NC_J9") (pintype "passive"))
    )
    (net (code "95") (name "unconnected-(IC27-NC-PadL1)") (class "Default")
      (node (ref "IC27") (pin "L1") (pinfunction "NC_L1") (pintype "passive"))
    )
    (net (code "96") (name "unconnected-(IC27-NC-PadL9)") (class "Default")
      (node (ref "IC27") (pin "L9") (pinfunction "NC_L9") (pintype "passive"))
    )
    (net (code "97") (name "unconnected-(IC27-NC-PadM7)") (class "Default")
      (node (ref "IC27") (pin "M7") (pinfunction "NC_M7") (pintype "passive"))
    )
  )
)
